# imxbbmmc.net
KiCad netlist of a schematic drawn in Altium Designer
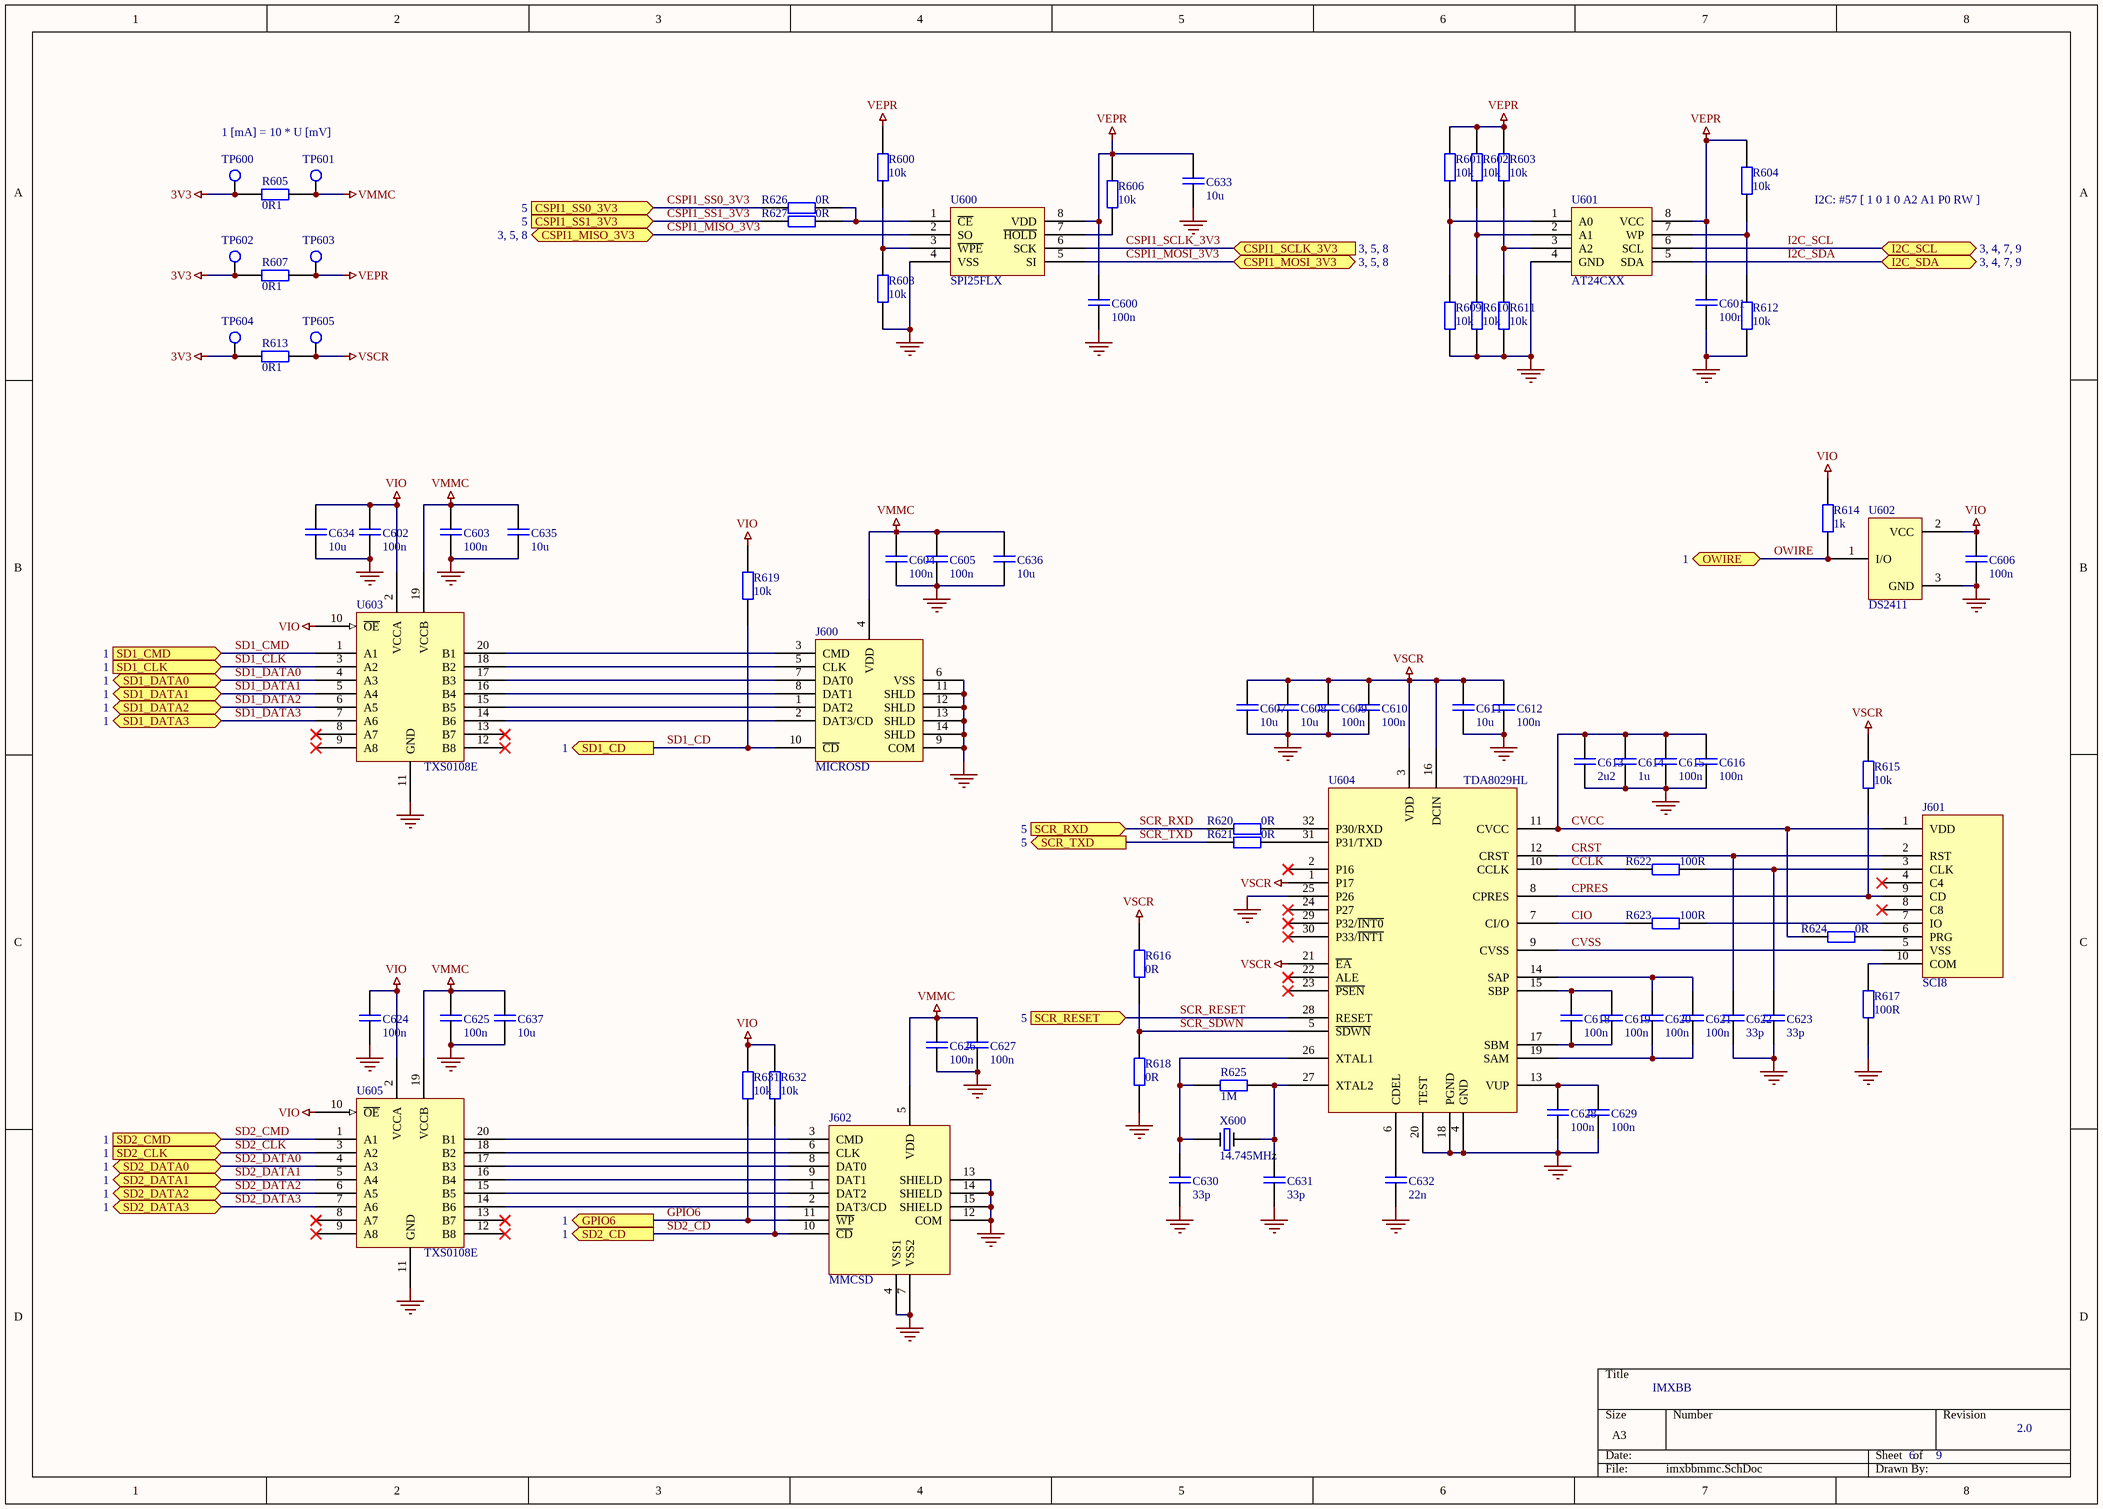
[diagram p0: imxbbmmc.SchDoc]

(export (version "E")
  (design (tool "Eeschema 10.0.6"))
  (components
    (comp (ref "C600") (value "100n") (footprint "0603") (libsource (lib "imxbb") (part "C")))
    (comp (ref "C601") (value "100n") (footprint "0603") (libsource (lib "imxbb") (part "C")))
    (comp (ref "C602") (value "100n") (footprint "0603") (libsource (lib "imxbb") (part "C")))
    (comp (ref "C603") (value "100n") (footprint "0603") (libsource (lib "imxbb") (part "C")))
    (comp (ref "C604") (value "100n") (footprint "0603") (libsource (lib "imxbb") (part "C")))
    (comp (ref "C605") (value "100n") (footprint "0603") (libsource (lib "imxbb") (part "C")))
    (comp (ref "C606") (value "100n") (footprint "0603") (libsource (lib "imxbb") (part "C")))
    (comp (ref "C607") (value "10u") (footprint "0805") (libsource (lib "imxbb") (part "C")))
    (comp (ref "C608") (value "10u") (footprint "0805") (libsource (lib "imxbb") (part "C")))
    (comp (ref "C609") (value "100n") (footprint "0603") (libsource (lib "imxbb") (part "C")))
    (comp (ref "C610") (value "100n") (footprint "0603") (libsource (lib "imxbb") (part "C")))
    (comp (ref "C611") (value "10u") (footprint "0805") (libsource (lib "imxbb") (part "C")))
    (comp (ref "C612") (value "100n") (footprint "0603") (libsource (lib "imxbb") (part "C")))
    (comp (ref "C613") (value "2u2") (footprint "0603") (libsource (lib "imxbb") (part "C")))
    (comp (ref "C614") (value "1u") (footprint "0603") (libsource (lib "imxbb") (part "C")))
    (comp (ref "C615") (value "100n") (footprint "0603") (libsource (lib "imxbb") (part "C")))
    (comp (ref "C616") (value "100n") (footprint "0603") (libsource (lib "imxbb") (part "C")))
    (comp (ref "C618") (value "100n") (footprint "0603") (libsource (lib "imxbb") (part "C")))
    (comp (ref "C619") (value "100n") (footprint "0603") (libsource (lib "imxbb") (part "C")))
    (comp (ref "C620") (value "100n") (footprint "0603") (libsource (lib "imxbb") (part "C")))
    (comp (ref "C621") (value "100n") (footprint "0603") (libsource (lib "imxbb") (part "C")))
    (comp (ref "C622") (value "33p") (footprint "0603") (libsource (lib "imxbb") (part "C")))
    (comp (ref "C623") (value "33p") (footprint "0603") (libsource (lib "imxbb") (part "C")))
    (comp (ref "C624") (value "100n") (footprint "0603") (libsource (lib "imxbb") (part "C")))
    (comp (ref "C625") (value "100n") (footprint "0603") (libsource (lib "imxbb") (part "C")))
    (comp (ref "C626") (value "100n") (footprint "0603") (libsource (lib "imxbb") (part "C")))
    (comp (ref "C627") (value "100n") (footprint "0603") (libsource (lib "imxbb") (part "C")))
    (comp (ref "C628") (value "100n") (footprint "0603") (libsource (lib "imxbb") (part "C")))
    (comp (ref "C629") (value "100n") (footprint "0603") (libsource (lib "imxbb") (part "C")))
    (comp (ref "C630") (value "33p") (footprint "0603") (libsource (lib "imxbb") (part "C")))
    (comp (ref "C631") (value "33p") (footprint "0603") (libsource (lib "imxbb") (part "C")))
    (comp (ref "C632") (value "22n") (footprint "0603") (libsource (lib "imxbb") (part "C")))
    (comp (ref "C633") (value "10u") (footprint "0805") (libsource (lib "imxbb") (part "C")))
    (comp (ref "C634") (value "10u") (footprint "0805") (libsource (lib "imxbb") (part "C")))
    (comp (ref "C635") (value "10u") (footprint "0805") (libsource (lib "imxbb") (part "C")))
    (comp (ref "C636") (value "10u") (footprint "0805") (libsource (lib "imxbb") (part "C")))
    (comp (ref "C637") (value "10u") (footprint "0805") (libsource (lib "imxbb") (part "C")))
    (comp (ref "J600") (value "MICROSD") (footprint "uSD10") (libsource (lib "imxbb") (part "MICROSD")))
    (comp (ref "J601") (value "SCI8") (footprint "SCI8F") (libsource (lib "imxbb") (part "SCI8")))
    (comp (ref "J602") (value "MMCSD") (footprint "SDCMF-109") (libsource (lib "imxbb") (part "MMCSD")))
    (comp (ref "R600") (value "10k") (footprint "0603") (libsource (lib "") (part "R_3")))
    (comp (ref "R601") (value "10k") (footprint "0603") (libsource (lib "") (part "R_3")))
    (comp (ref "R602") (value "10k") (footprint "0603") (libsource (lib "") (part "R_3")))
    (comp (ref "R603") (value "10k") (footprint "0603") (libsource (lib "") (part "R_3")))
    (comp (ref "R604") (value "10k") (footprint "0603") (libsource (lib "") (part "R_3")))
    (comp (ref "R605") (value "0R1") (footprint "0603") (libsource (lib "imxbb") (part "R")))
    (comp (ref "R606") (value "10k") (footprint "0603") (libsource (lib "") (part "R_3")))
    (comp (ref "R607") (value "0R1") (footprint "0603") (libsource (lib "imxbb") (part "R")))
    (comp (ref "R608") (value "10k") (footprint "0603") (libsource (lib "") (part "R_3")))
    (comp (ref "R609") (value "10k") (footprint "0603") (libsource (lib "") (part "R_3")))
    (comp (ref "R610") (value "10k") (footprint "0603") (libsource (lib "") (part "R_3")))
    (comp (ref "R611") (value "10k") (footprint "0603") (libsource (lib "") (part "R_3")))
    (comp (ref "R612") (value "10k") (footprint "0603") (libsource (lib "") (part "R_3")))
    (comp (ref "R613") (value "0R1") (footprint "0603") (libsource (lib "imxbb") (part "R")))
    (comp (ref "R614") (value "1k") (footprint "0603") (libsource (lib "") (part "R_3")))
    (comp (ref "R615") (value "10k") (footprint "0603") (libsource (lib "") (part "R_4")))
    (comp (ref "R616") (value "0R") (footprint "0603") (libsource (lib "") (part "R_4")))
    (comp (ref "R617") (value "100R") (footprint "0603") (libsource (lib "") (part "R_4")))
    (comp (ref "R618") (value "0R") (footprint "0603") (libsource (lib "") (part "R_4")))
    (comp (ref "R619") (value "10k") (footprint "0603") (libsource (lib "") (part "R_3")))
    (comp (ref "R620") (value "0R") (footprint "0603") (libsource (lib "") (part "R_1")))
    (comp (ref "R621") (value "0R") (footprint "0603") (libsource (lib "") (part "R_1")))
    (comp (ref "R622") (value "100R") (footprint "0603") (libsource (lib "") (part "R_1")))
    (comp (ref "R623") (value "100R") (footprint "0603") (libsource (lib "") (part "R_1")))
    (comp (ref "R624") (value "0R") (footprint "0603") (libsource (lib "") (part "R_1")))
    (comp (ref "R625") (value "1M") (footprint "0603") (libsource (lib "") (part "R_2")))
    (comp (ref "R626") (value "0R") (footprint "0603") (libsource (lib "") (part "R_1")))
    (comp (ref "R627") (value "0R") (footprint "0603") (libsource (lib "") (part "R_1")))
    (comp (ref "R631") (value "10k") (footprint "0603") (libsource (lib "") (part "R_3")))
    (comp (ref "R632") (value "10k") (footprint "0603") (libsource (lib "") (part "R_3")))
    (comp (ref "TP600")
      (value "TESTPOINT")
      (footprint "TESTPOINT_2mm")
      (description "Testpoint pad")
      (libsource (lib "imxbb") (part "TESTPOINT"))
    )
    (comp (ref "TP601")
      (value "TESTPOINT")
      (footprint "TESTPOINT_2mm")
      (description "Testpoint pad")
      (libsource (lib "imxbb") (part "TESTPOINT"))
    )
    (comp (ref "TP602")
      (value "TESTPOINT")
      (footprint "TESTPOINT_2mm")
      (description "Testpoint pad")
      (libsource (lib "imxbb") (part "TESTPOINT"))
    )
    (comp (ref "TP603")
      (value "TESTPOINT")
      (footprint "TESTPOINT_2mm")
      (description "Testpoint pad")
      (libsource (lib "imxbb") (part "TESTPOINT"))
    )
    (comp (ref "TP604")
      (value "TESTPOINT")
      (footprint "TESTPOINT_2mm")
      (description "Testpoint pad")
      (libsource (lib "imxbb") (part "TESTPOINT"))
    )
    (comp (ref "TP605")
      (value "TESTPOINT")
      (footprint "TESTPOINT_2mm")
      (description "Testpoint pad")
      (libsource (lib "imxbb") (part "TESTPOINT"))
    )
    (comp (ref "U600") (value "SPI25FLX") (footprint "SOIC8") (libsource (lib "imxbb") (part "SPI25FLX")))
    (comp (ref "U601") (value "AT24CXX") (footprint "SOIC8") (libsource (lib "imxbb") (part "AT24CXX")))
    (comp (ref "U602") (value "DS2411") (footprint "SOT23") (libsource (lib "imxbb") (part "DS2411")))
    (comp (ref "U603") (value "TXS0108E") (footprint "TSSOP20") (libsource (lib "imxbb") (part "TXS0108E")))
    (comp (ref "U604") (value "TDA8029HL") (footprint "LQFP32") (libsource (lib "imxbb") (part "TDA8029HL")))
    (comp (ref "U605") (value "TXS0108E") (footprint "TSSOP20") (libsource (lib "imxbb") (part "TXS0108E")))
    (comp (ref "X600") (value "14.745MHz") (footprint "HC494H") (libsource (lib "imxbb") (part "XTAL")))
  )
  (nets
    (net (code "1") (name "/CCLK") (class "Default")
      (node (ref "R622") (pin "1") (pinfunction "1_1") (pintype "passive"))
      (node (ref "U604") (pin "10") (pinfunction "CCLK_10") (pintype "passive"))
    )
    (net (code "2") (name "/CIO") (class "Default")
      (node (ref "R623") (pin "1") (pinfunction "1_1") (pintype "passive"))
      (node (ref "U604") (pin "7") (pinfunction "CI/O_7") (pintype "passive"))
    )
    (net (code "3") (name "/CPRES") (class "Default")
      (node (ref "J601") (pin "9") (pinfunction "CD_9") (pintype "passive"))
      (node (ref "R615") (pin "1") (pinfunction "1_1") (pintype "passive"))
      (node (ref "U604") (pin "8") (pinfunction "CPRES_8") (pintype "passive"))
    )
    (net (code "4") (name "/CRST") (class "Default")
      (node (ref "C622") (pin "2") (pinfunction "2_2") (pintype "passive"))
      (node (ref "J601") (pin "2") (pinfunction "RST_2") (pintype "passive"))
      (node (ref "U604") (pin "12") (pinfunction "CRST_12") (pintype "passive"))
    )
    (net (code "5") (name "/CSPI1_MISO_3V3") (class "Default")
      (node (ref "U600") (pin "2") (pinfunction "SO_2") (pintype "passive"))
    )
    (net (code "6") (name "/CSPI1_MOSI_3V3") (class "Default")
      (node (ref "U600") (pin "5") (pinfunction "SI_5") (pintype "passive"))
    )
    (net (code "7") (name "/CSPI1_SCLK_3V3") (class "Default")
      (node (ref "U600") (pin "6") (pinfunction "SCK_6") (pintype "passive"))
    )
    (net (code "8") (name "/CSPI1_SS0_3V3") (class "Default")
      (node (ref "R626") (pin "1") (pinfunction "1_1") (pintype "passive"))
    )
    (net (code "9") (name "/CSPI1_SS1_3V3") (class "Default")
      (node (ref "R627") (pin "1") (pinfunction "1_1") (pintype "passive"))
    )
    (net (code "10") (name "/CVCC") (class "Default")
      (node (ref "C613") (pin "2") (pinfunction "2_2") (pintype "passive"))
      (node (ref "C614") (pin "2") (pinfunction "2_2") (pintype "passive"))
      (node (ref "C615") (pin "2") (pinfunction "2_2") (pintype "passive"))
      (node (ref "C616") (pin "2") (pinfunction "2_2") (pintype "passive"))
      (node (ref "J601") (pin "1") (pinfunction "VDD_1") (pintype "passive"))
      (node (ref "R624") (pin "1") (pinfunction "1_1") (pintype "passive"))
      (node (ref "U604") (pin "11") (pinfunction "CVCC_11") (pintype "passive"))
    )
    (net (code "11") (name "/CVSS") (class "Default")
      (node (ref "J601") (pin "5") (pinfunction "VSS_5") (pintype "passive"))
      (node (ref "U604") (pin "9") (pinfunction "CVSS_9") (pintype "passive"))
    )
    (net (code "12") (name "/GPIO6") (class "Default")
      (node (ref "J602") (pin "11") (pinfunction "~{WP}_11") (pintype "passive"))
      (node (ref "R631") (pin "2") (pinfunction "2_2") (pintype "passive"))
    )
    (net (code "13") (name "/I2C_SCL") (class "Default")
      (node (ref "U601") (pin "6") (pinfunction "SCL_6") (pintype "passive"))
    )
    (net (code "14") (name "/I2C_SDA") (class "Default")
      (node (ref "U601") (pin "5") (pinfunction "SDA_5") (pintype "passive"))
    )
    (net (code "15") (name "/OWIRE") (class "Default")
      (node (ref "R614") (pin "2") (pinfunction "2_2") (pintype "passive"))
      (node (ref "U602") (pin "1") (pinfunction "I/O_1") (pintype "passive"))
    )
    (net (code "16") (name "/SCR_RESET") (class "Default")
      (node (ref "U604") (pin "28") (pinfunction "RESET_28") (pintype "passive"))
    )
    (net (code "17") (name "/SCR_RXD") (class "Default")
      (node (ref "R620") (pin "1") (pinfunction "1_1") (pintype "passive"))
    )
    (net (code "18") (name "/SCR_SDWN") (class "Default")
      (node (ref "R616") (pin "1") (pinfunction "1_1") (pintype "passive"))
      (node (ref "R618") (pin "2") (pinfunction "2_2") (pintype "passive"))
      (node (ref "U604") (pin "5") (pinfunction "~{SDWN}_5") (pintype "passive"))
    )
    (net (code "19") (name "/SCR_TXD") (class "Default")
      (node (ref "R621") (pin "1") (pinfunction "1_1") (pintype "passive"))
    )
    (net (code "20") (name "/SD1_CD") (class "Default")
      (node (ref "J600") (pin "10") (pinfunction "~{CD}_10") (pintype "passive"))
      (node (ref "R619") (pin "2") (pinfunction "2_2") (pintype "passive"))
    )
    (net (code "21") (name "/SD1_CLK") (class "Default")
      (node (ref "U603") (pin "3") (pinfunction "A2_3") (pintype "passive"))
    )
    (net (code "22") (name "/SD1_CMD") (class "Default")
      (node (ref "U603") (pin "1") (pinfunction "A1_1") (pintype "passive"))
    )
    (net (code "23") (name "/SD1_DATA0") (class "Default")
      (node (ref "U603") (pin "4") (pinfunction "A3_4") (pintype "passive"))
    )
    (net (code "24") (name "/SD1_DATA1") (class "Default")
      (node (ref "U603") (pin "5") (pinfunction "A4_5") (pintype "passive"))
    )
    (net (code "25") (name "/SD1_DATA2") (class "Default")
      (node (ref "U603") (pin "6") (pinfunction "A5_6") (pintype "passive"))
    )
    (net (code "26") (name "/SD1_DATA3") (class "Default")
      (node (ref "U603") (pin "7") (pinfunction "A6_7") (pintype "passive"))
    )
    (net (code "27") (name "/SD2_CD") (class "Default")
      (node (ref "J602") (pin "10") (pinfunction "~{CD}_10") (pintype "passive"))
      (node (ref "R632") (pin "2") (pinfunction "2_2") (pintype "passive"))
    )
    (net (code "28") (name "/SD2_CLK") (class "Default")
      (node (ref "U605") (pin "3") (pinfunction "A2_3") (pintype "passive"))
    )
    (net (code "29") (name "/SD2_CMD") (class "Default")
      (node (ref "U605") (pin "1") (pinfunction "A1_1") (pintype "passive"))
    )
    (net (code "30") (name "/SD2_DATA0") (class "Default")
      (node (ref "U605") (pin "4") (pinfunction "A3_4") (pintype "passive"))
    )
    (net (code "31") (name "/SD2_DATA1") (class "Default")
      (node (ref "U605") (pin "5") (pinfunction "A4_5") (pintype "passive"))
    )
    (net (code "32") (name "/SD2_DATA2") (class "Default")
      (node (ref "U605") (pin "6") (pinfunction "A5_6") (pintype "passive"))
    )
    (net (code "33") (name "/SD2_DATA3") (class "Default")
      (node (ref "U605") (pin "7") (pinfunction "A6_7") (pintype "passive"))
    )
    (net (code "34") (name "3V3") (class "Default")
      (node (ref "R605") (pin "1") (pinfunction "1_1") (pintype "passive"))
      (node (ref "R607") (pin "1") (pinfunction "1_1") (pintype "passive"))
      (node (ref "R613") (pin "1") (pinfunction "1_1") (pintype "passive"))
      (node (ref "TP600") (pin "1") (pinfunction "1_1") (pintype "passive"))
      (node (ref "TP602") (pin "1") (pinfunction "1_1") (pintype "passive"))
      (node (ref "TP604") (pin "1") (pinfunction "1_1") (pintype "passive"))
    )
    (net (code "35") (name "GND") (class "Default")
      (node (ref "C600") (pin "1") (pinfunction "1_1") (pintype "passive"))
      (node (ref "C601") (pin "1") (pinfunction "1_1") (pintype "passive"))
      (node (ref "C602") (pin "1") (pinfunction "1_1") (pintype "passive"))
      (node (ref "C603") (pin "1") (pinfunction "1_1") (pintype "passive"))
      (node (ref "C604") (pin "1") (pinfunction "1_1") (pintype "passive"))
      (node (ref "C605") (pin "1") (pinfunction "1_1") (pintype "passive"))
      (node (ref "C606") (pin "1") (pinfunction "1_1") (pintype "passive"))
      (node (ref "C607") (pin "1") (pinfunction "1_1") (pintype "passive"))
      (node (ref "C608") (pin "1") (pinfunction "1_1") (pintype "passive"))
      (node (ref "C609") (pin "1") (pinfunction "1_1") (pintype "passive"))
      (node (ref "C610") (pin "1") (pinfunction "1_1") (pintype "passive"))
      (node (ref "C611") (pin "1") (pinfunction "1_1") (pintype "passive"))
      (node (ref "C612") (pin "1") (pinfunction "1_1") (pintype "passive"))
      (node (ref "C613") (pin "1") (pinfunction "1_1") (pintype "passive"))
      (node (ref "C614") (pin "1") (pinfunction "1_1") (pintype "passive"))
      (node (ref "C615") (pin "1") (pinfunction "1_1") (pintype "passive"))
      (node (ref "C616") (pin "1") (pinfunction "1_1") (pintype "passive"))
      (node (ref "C622") (pin "1") (pinfunction "1_1") (pintype "passive"))
      (node (ref "C623") (pin "1") (pinfunction "1_1") (pintype "passive"))
      (node (ref "C624") (pin "1") (pinfunction "1_1") (pintype "passive"))
      (node (ref "C625") (pin "1") (pinfunction "1_1") (pintype "passive"))
      (node (ref "C626") (pin "1") (pinfunction "1_1") (pintype "passive"))
      (node (ref "C627") (pin "1") (pinfunction "1_1") (pintype "passive"))
      (node (ref "C628") (pin "1") (pinfunction "1_1") (pintype "passive"))
      (node (ref "C629") (pin "1") (pinfunction "1_1") (pintype "passive"))
      (node (ref "C630") (pin "1") (pinfunction "1_1") (pintype "passive"))
      (node (ref "C631") (pin "1") (pinfunction "1_1") (pintype "passive"))
      (node (ref "C632") (pin "1") (pinfunction "1_1") (pintype "passive"))
      (node (ref "C633") (pin "1") (pinfunction "1_1") (pintype "passive"))
      (node (ref "C634") (pin "1") (pinfunction "1_1") (pintype "passive"))
      (node (ref "C635") (pin "1") (pinfunction "1_1") (pintype "passive"))
      (node (ref "C636") (pin "1") (pinfunction "1_1") (pintype "passive"))
      (node (ref "C637") (pin "1") (pinfunction "1_1") (pintype "passive"))
      (node (ref "J600") (pin "11") (pinfunction "SHLD_11") (pintype "passive"))
      (node (ref "J600") (pin "12") (pinfunction "SHLD_12") (pintype "passive"))
      (node (ref "J600") (pin "13") (pinfunction "SHLD_13") (pintype "passive"))
      (node (ref "J600") (pin "14") (pinfunction "SHLD_14") (pintype "passive"))
      (node (ref "J600") (pin "6") (pinfunction "VSS_6") (pintype "passive"))
      (node (ref "J600") (pin "9") (pinfunction "COM_9") (pintype "passive"))
      (node (ref "J602") (pin "12") (pinfunction "COM_12") (pintype "passive"))
      (node (ref "J602") (pin "13") (pinfunction "SHIELD_13") (pintype "passive"))
      (node (ref "J602") (pin "14") (pinfunction "SHIELD_14") (pintype "passive"))
      (node (ref "J602") (pin "15") (pinfunction "SHIELD_15") (pintype "passive"))
      (node (ref "J602") (pin "4") (pinfunction "VSS1_4") (pintype "passive"))
      (node (ref "J602") (pin "7") (pinfunction "VSS2_7") (pintype "passive"))
      (node (ref "R608") (pin "2") (pinfunction "2_2") (pintype "passive"))
      (node (ref "R609") (pin "2") (pinfunction "2_2") (pintype "passive"))
      (node (ref "R610") (pin "2") (pinfunction "2_2") (pintype "passive"))
      (node (ref "R611") (pin "2") (pinfunction "2_2") (pintype "passive"))
      (node (ref "R612") (pin "2") (pinfunction "2_2") (pintype "passive"))
      (node (ref "R617") (pin "1") (pinfunction "1_1") (pintype "passive"))
      (node (ref "R618") (pin "1") (pinfunction "1_1") (pintype "passive"))
      (node (ref "U600") (pin "4") (pinfunction "VSS_4") (pintype "passive"))
      (node (ref "U601") (pin "4") (pinfunction "GND_4") (pintype "passive"))
      (node (ref "U602") (pin "3") (pinfunction "GND_3") (pintype "passive"))
      (node (ref "U603") (pin "11") (pinfunction "GND_11") (pintype "power_in"))
      (node (ref "U604") (pin "18") (pinfunction "PGND_18") (pintype "passive"))
      (node (ref "U604") (pin "20") (pinfunction "TEST_20") (pintype "passive"))
      (node (ref "U604") (pin "25") (pinfunction "P26_25") (pintype "passive"))
      (node (ref "U604") (pin "4") (pinfunction "GND_4") (pintype "passive"))
      (node (ref "U605") (pin "11") (pinfunction "GND_11") (pintype "power_in"))
    )
    (net (code "36") (name "Net-(J600-CLK)") (class "Default")
      (node (ref "J600") (pin "5") (pinfunction "CLK_5") (pintype "passive"))
      (node (ref "U603") (pin "18") (pinfunction "B2_18") (pintype "passive"))
    )
    (net (code "37") (name "Net-(J600-CMD)") (class "Default")
      (node (ref "J600") (pin "3") (pinfunction "CMD_3") (pintype "passive"))
      (node (ref "U603") (pin "20") (pinfunction "B1_20") (pintype "passive"))
    )
    (net (code "38") (name "Net-(J600-DAT0)") (class "Default")
      (node (ref "J600") (pin "7") (pinfunction "DAT0_7") (pintype "passive"))
      (node (ref "U603") (pin "17") (pinfunction "B3_17") (pintype "passive"))
    )
    (net (code "39") (name "Net-(J600-DAT1)") (class "Default")
      (node (ref "J600") (pin "8") (pinfunction "DAT1_8") (pintype "passive"))
      (node (ref "U603") (pin "16") (pinfunction "B4_16") (pintype "passive"))
    )
    (net (code "40") (name "Net-(J600-DAT2)") (class "Default")
      (node (ref "J600") (pin "1") (pinfunction "DAT2_1") (pintype "passive"))
      (node (ref "U603") (pin "15") (pinfunction "B5_15") (pintype "passive"))
    )
    (net (code "41") (name "Net-(J600-DAT3{slash}CD)") (class "Default")
      (node (ref "J600") (pin "2") (pinfunction "DAT3/CD_2") (pintype "passive"))
      (node (ref "U603") (pin "14") (pinfunction "B6_14") (pintype "passive"))
    )
    (net (code "42") (name "Net-(J601-CLK)") (class "Default")
      (node (ref "C623") (pin "2") (pinfunction "2_2") (pintype "passive"))
      (node (ref "J601") (pin "3") (pinfunction "CLK_3") (pintype "passive"))
      (node (ref "R622") (pin "2") (pinfunction "2_2") (pintype "passive"))
    )
    (net (code "43") (name "Net-(J601-COM)") (class "Default")
      (node (ref "J601") (pin "10") (pinfunction "COM_10") (pintype "passive"))
      (node (ref "R617") (pin "2") (pinfunction "2_2") (pintype "passive"))
    )
    (net (code "44") (name "Net-(J601-IO)") (class "Default")
      (node (ref "J601") (pin "7") (pinfunction "IO_7") (pintype "passive"))
      (node (ref "R623") (pin "2") (pinfunction "2_2") (pintype "passive"))
    )
    (net (code "45") (name "Net-(J601-PRG)") (class "Default")
      (node (ref "J601") (pin "6") (pinfunction "PRG_6") (pintype "passive"))
      (node (ref "R624") (pin "2") (pinfunction "2_2") (pintype "passive"))
    )
    (net (code "46") (name "Net-(J602-CLK)") (class "Default")
      (node (ref "J602") (pin "6") (pinfunction "CLK_6") (pintype "passive"))
      (node (ref "U605") (pin "18") (pinfunction "B2_18") (pintype "passive"))
    )
    (net (code "47") (name "Net-(J602-CMD)") (class "Default")
      (node (ref "J602") (pin "3") (pinfunction "CMD_3") (pintype "passive"))
      (node (ref "U605") (pin "20") (pinfunction "B1_20") (pintype "passive"))
    )
    (net (code "48") (name "Net-(J602-DAT0)") (class "Default")
      (node (ref "J602") (pin "8") (pinfunction "DAT0_8") (pintype "passive"))
      (node (ref "U605") (pin "17") (pinfunction "B3_17") (pintype "passive"))
    )
    (net (code "49") (name "Net-(J602-DAT1)") (class "Default")
      (node (ref "J602") (pin "9") (pinfunction "DAT1_9") (pintype "passive"))
      (node (ref "U605") (pin "16") (pinfunction "B4_16") (pintype "passive"))
    )
    (net (code "50") (name "Net-(J602-DAT2)") (class "Default")
      (node (ref "J602") (pin "1") (pinfunction "DAT2_1") (pintype "passive"))
      (node (ref "U605") (pin "15") (pinfunction "B5_15") (pintype "passive"))
    )
    (net (code "51") (name "Net-(J602-DAT3{slash}CD)") (class "Default")
      (node (ref "J602") (pin "2") (pinfunction "DAT3/CD_2") (pintype "passive"))
      (node (ref "U605") (pin "14") (pinfunction "B6_14") (pintype "passive"))
    )
    (net (code "52") (name "Net-(U600-~{CE})") (class "Default")
      (node (ref "R626") (pin "2") (pinfunction "2_2") (pintype "passive"))
      (node (ref "R627") (pin "2") (pinfunction "2_2") (pintype "passive"))
      (node (ref "U600") (pin "1") (pinfunction "~{CE}_1") (pintype "passive"))
    )
    (net (code "53") (name "Net-(U600-~{HOLD})") (class "Default")
      (node (ref "R606") (pin "2") (pinfunction "2_2") (pintype "passive"))
      (node (ref "U600") (pin "7") (pinfunction "~{HOLD}_7") (pintype "passive"))
    )
    (net (code "54") (name "Net-(U600-~{WPE})") (class "Default")
      (node (ref "R600") (pin "2") (pinfunction "2_2") (pintype "passive"))
      (node (ref "R608") (pin "1") (pinfunction "1_1") (pintype "passive"))
      (node (ref "U600") (pin "3") (pinfunction "~{WPE}_3") (pintype "passive"))
    )
    (net (code "55") (name "Net-(U601-A0)") (class "Default")
      (node (ref "R601") (pin "2") (pinfunction "2_2") (pintype "passive"))
      (node (ref "R609") (pin "1") (pinfunction "1_1") (pintype "passive"))
      (node (ref "U601") (pin "1") (pinfunction "A0_1") (pintype "passive"))
    )
    (net (code "56") (name "Net-(U601-A1)") (class "Default")
      (node (ref "R602") (pin "2") (pinfunction "2_2") (pintype "passive"))
      (node (ref "R610") (pin "1") (pinfunction "1_1") (pintype "passive"))
      (node (ref "U601") (pin "2") (pinfunction "A1_2") (pintype "passive"))
    )
    (net (code "57") (name "Net-(U601-A2)") (class "Default")
      (node (ref "R603") (pin "2") (pinfunction "2_2") (pintype "passive"))
      (node (ref "R611") (pin "1") (pinfunction "1_1") (pintype "passive"))
      (node (ref "U601") (pin "3") (pinfunction "A2_3") (pintype "passive"))
    )
    (net (code "58") (name "Net-(U601-WP)") (class "Default")
      (node (ref "R604") (pin "2") (pinfunction "2_2") (pintype "passive"))
      (node (ref "R612") (pin "1") (pinfunction "1_1") (pintype "passive"))
      (node (ref "U601") (pin "7") (pinfunction "WP_7") (pintype "passive"))
    )
    (net (code "59") (name "Net-(U604-CDEL)") (class "Default")
      (node (ref "C632") (pin "2") (pinfunction "2_2") (pintype "passive"))
      (node (ref "U604") (pin "6") (pinfunction "CDEL_6") (pintype "passive"))
    )
    (net (code "60") (name "Net-(U604-P30{slash}RXD)") (class "Default")
      (node (ref "R620") (pin "2") (pinfunction "2_2") (pintype "passive"))
      (node (ref "U604") (pin "32") (pinfunction "P30/RXD_32") (pintype "passive"))
    )
    (net (code "61") (name "Net-(U604-P31{slash}TXD)") (class "Default")
      (node (ref "R621") (pin "2") (pinfunction "2_2") (pintype "passive"))
      (node (ref "U604") (pin "31") (pinfunction "P31/TXD_31") (pintype "passive"))
    )
    (net (code "62") (name "Net-(U604-SAM)") (class "Default")
      (node (ref "C620") (pin "1") (pinfunction "1_1") (pintype "passive"))
      (node (ref "C621") (pin "1") (pinfunction "1_1") (pintype "passive"))
      (node (ref "U604") (pin "19") (pinfunction "SAM_19") (pintype "passive"))
    )
    (net (code "63") (name "Net-(U604-SAP)") (class "Default")
      (node (ref "C620") (pin "2") (pinfunction "2_2") (pintype "passive"))
      (node (ref "C621") (pin "2") (pinfunction "2_2") (pintype "passive"))
      (node (ref "U604") (pin "14") (pinfunction "SAP_14") (pintype "passive"))
    )
    (net (code "64") (name "Net-(U604-SBM)") (class "Default")
      (node (ref "C618") (pin "1") (pinfunction "1_1") (pintype "passive"))
      (node (ref "C619") (pin "1") (pinfunction "1_1") (pintype "passive"))
      (node (ref "U604") (pin "17") (pinfunction "SBM_17") (pintype "passive"))
    )
    (net (code "65") (name "Net-(U604-SBP)") (class "Default")
      (node (ref "C618") (pin "2") (pinfunction "2_2") (pintype "passive"))
      (node (ref "C619") (pin "2") (pinfunction "2_2") (pintype "passive"))
      (node (ref "U604") (pin "15") (pinfunction "SBP_15") (pintype "passive"))
    )
    (net (code "66") (name "Net-(U604-VUP)") (class "Default")
      (node (ref "C628") (pin "2") (pinfunction "2_2") (pintype "passive"))
      (node (ref "C629") (pin "2") (pinfunction "2_2") (pintype "passive"))
      (node (ref "U604") (pin "13") (pinfunction "VUP_13") (pintype "passive"))
    )
    (net (code "67") (name "Net-(U604-XTAL1)") (class "Default")
      (node (ref "C630") (pin "2") (pinfunction "2_2") (pintype "passive"))
      (node (ref "R625") (pin "2") (pinfunction "2_2") (pintype "passive"))
      (node (ref "U604") (pin "26") (pinfunction "XTAL1_26") (pintype "passive"))
      (node (ref "X600") (pin "1") (pinfunction "1_1") (pintype "passive"))
    )
    (net (code "68") (name "Net-(U604-XTAL2)") (class "Default")
      (node (ref "C631") (pin "2") (pinfunction "2_2") (pintype "passive"))
      (node (ref "R625") (pin "1") (pinfunction "1_1") (pintype "passive"))
      (node (ref "U604") (pin "27") (pinfunction "XTAL2_27") (pintype "passive"))
      (node (ref "X600") (pin "2") (pinfunction "2_2") (pintype "passive"))
    )
    (net (code "69") (name "VEPR") (class "Default")
      (node (ref "C600") (pin "2") (pinfunction "2_2") (pintype "passive"))
      (node (ref "C601") (pin "2") (pinfunction "2_2") (pintype "passive"))
      (node (ref "C633") (pin "2") (pinfunction "2_2") (pintype "passive"))
      (node (ref "R600") (pin "1") (pinfunction "1_1") (pintype "passive"))
      (node (ref "R601") (pin "1") (pinfunction "1_1") (pintype "passive"))
      (node (ref "R602") (pin "1") (pinfunction "1_1") (pintype "passive"))
      (node (ref "R603") (pin "1") (pinfunction "1_1") (pintype "passive"))
      (node (ref "R604") (pin "1") (pinfunction "1_1") (pintype "passive"))
      (node (ref "R606") (pin "1") (pinfunction "1_1") (pintype "passive"))
      (node (ref "R607") (pin "2") (pinfunction "2_2") (pintype "passive"))
      (node (ref "TP603") (pin "1") (pinfunction "1_1") (pintype "passive"))
      (node (ref "U600") (pin "8") (pinfunction "VDD_8") (pintype "passive"))
      (node (ref "U601") (pin "8") (pinfunction "VCC_8") (pintype "passive"))
    )
    (net (code "70") (name "VIO") (class "Default")
      (node (ref "C602") (pin "2") (pinfunction "2_2") (pintype "passive"))
      (node (ref "C606") (pin "2") (pinfunction "2_2") (pintype "passive"))
      (node (ref "C624") (pin "2") (pinfunction "2_2") (pintype "passive"))
      (node (ref "C634") (pin "2") (pinfunction "2_2") (pintype "passive"))
      (node (ref "R614") (pin "1") (pinfunction "1_1") (pintype "passive"))
      (node (ref "R619") (pin "1") (pinfunction "1_1") (pintype "passive"))
      (node (ref "R631") (pin "1") (pinfunction "1_1") (pintype "passive"))
      (node (ref "R632") (pin "1") (pinfunction "1_1") (pintype "passive"))
      (node (ref "U602") (pin "2") (pinfunction "VCC_2") (pintype "passive"))
      (node (ref "U603") (pin "10") (pinfunction "~{OE}_10") (pintype "input"))
      (node (ref "U603") (pin "2") (pinfunction "VCCA_2") (pintype "power_in"))
      (node (ref "U605") (pin "10") (pinfunction "~{OE}_10") (pintype "input"))
      (node (ref "U605") (pin "2") (pinfunction "VCCA_2") (pintype "power_in"))
    )
    (net (code "71") (name "VMMC") (class "Default")
      (node (ref "C603") (pin "2") (pinfunction "2_2") (pintype "passive"))
      (node (ref "C604") (pin "2") (pinfunction "2_2") (pintype "passive"))
      (node (ref "C605") (pin "2") (pinfunction "2_2") (pintype "passive"))
      (node (ref "C625") (pin "2") (pinfunction "2_2") (pintype "passive"))
      (node (ref "C626") (pin "2") (pinfunction "2_2") (pintype "passive"))
      (node (ref "C627") (pin "2") (pinfunction "2_2") (pintype "passive"))
      (node (ref "C635") (pin "2") (pinfunction "2_2") (pintype "passive"))
      (node (ref "C636") (pin "2") (pinfunction "2_2") (pintype "passive"))
      (node (ref "C637") (pin "2") (pinfunction "2_2") (pintype "passive"))
      (node (ref "J600") (pin "4") (pinfunction "VDD_4") (pintype "passive"))
      (node (ref "J602") (pin "5") (pinfunction "VDD_5") (pintype "passive"))
      (node (ref "R605") (pin "2") (pinfunction "2_2") (pintype "passive"))
      (node (ref "TP601") (pin "1") (pinfunction "1_1") (pintype "passive"))
      (node (ref "U603") (pin "19") (pinfunction "VCCB_19") (pintype "power_in"))
      (node (ref "U605") (pin "19") (pinfunction "VCCB_19") (pintype "power_in"))
    )
    (net (code "72") (name "VSCR") (class "Default")
      (node (ref "C607") (pin "2") (pinfunction "2_2") (pintype "passive"))
      (node (ref "C608") (pin "2") (pinfunction "2_2") (pintype "passive"))
      (node (ref "C609") (pin "2") (pinfunction "2_2") (pintype "passive"))
      (node (ref "C610") (pin "2") (pinfunction "2_2") (pintype "passive"))
      (node (ref "C611") (pin "2") (pinfunction "2_2") (pintype "passive"))
      (node (ref "C612") (pin "2") (pinfunction "2_2") (pintype "passive"))
      (node (ref "R613") (pin "2") (pinfunction "2_2") (pintype "passive"))
      (node (ref "R615") (pin "2") (pinfunction "2_2") (pintype "passive"))
      (node (ref "R616") (pin "2") (pinfunction "2_2") (pintype "passive"))
      (node (ref "TP605") (pin "1") (pinfunction "1_1") (pintype "passive"))
      (node (ref "U604") (pin "1") (pinfunction "P17_1") (pintype "passive"))
      (node (ref "U604") (pin "16") (pinfunction "DCIN_16") (pintype "passive"))
      (node (ref "U604") (pin "21") (pinfunction "~{EA}_21") (pintype "passive"))
      (node (ref "U604") (pin "3") (pinfunction "VDD_3") (pintype "passive"))
    )
    (net (code "73") (name "unconnected-(J601-C4-Pad4)") (class "Default")
      (node (ref "J601") (pin "4") (pinfunction "C4_4") (pintype "passive+no_connect"))
    )
    (net (code "74") (name "unconnected-(J601-C8-Pad8)") (class "Default")
      (node (ref "J601") (pin "8") (pinfunction "C8_8") (pintype "passive+no_connect"))
    )
    (net (code "75") (name "unconnected-(U603-A7-Pad8)") (class "Default")
      (node (ref "U603") (pin "8") (pinfunction "A7_8") (pintype "passive+no_connect"))
    )
    (net (code "76") (name "unconnected-(U603-A8-Pad9)") (class "Default")
      (node (ref "U603") (pin "9") (pinfunction "A8_9") (pintype "passive+no_connect"))
    )
    (net (code "77") (name "unconnected-(U603-B7-Pad13)") (class "Default")
      (node (ref "U603") (pin "13") (pinfunction "B7_13") (pintype "passive+no_connect"))
    )
    (net (code "78") (name "unconnected-(U603-B8-Pad12)") (class "Default")
      (node (ref "U603") (pin "12") (pinfunction "B8_12") (pintype "passive+no_connect"))
    )
    (net (code "79") (name "unconnected-(U604-ALE-Pad22)") (class "Default")
      (node (ref "U604") (pin "22") (pinfunction "ALE_22") (pintype "passive+no_connect"))
    )
    (net (code "80") (name "unconnected-(U604-P16-Pad2)") (class "Default")
      (node (ref "U604") (pin "2") (pinfunction "P16_2") (pintype "passive+no_connect"))
    )
    (net (code "81") (name "unconnected-(U604-P27-Pad24)") (class "Default")
      (node (ref "U604") (pin "24") (pinfunction "P27_24") (pintype "passive+no_connect"))
    )
    (net (code "82") (name "unconnected-(U604-P32{slash}~{INT0}-Pad29)") (class "Default")
      (node (ref "U604") (pin "29") (pinfunction "P32/~{INT0}_29") (pintype "passive+no_connect"))
    )
    (net (code "83") (name "unconnected-(U604-P33{slash}~{INT1}-Pad30)") (class "Default")
      (node (ref "U604") (pin "30") (pinfunction "P33/~{INT1}_30") (pintype "passive+no_connect"))
    )
    (net (code "84") (name "unconnected-(U604-~{PSEN}-Pad23)") (class "Default")
      (node (ref "U604") (pin "23") (pinfunction "~{PSEN}_23") (pintype "passive+no_connect"))
    )
    (net (code "85") (name "unconnected-(U605-A7-Pad8)") (class "Default")
      (node (ref "U605") (pin "8") (pinfunction "A7_8") (pintype "passive+no_connect"))
    )
    (net (code "86") (name "unconnected-(U605-A8-Pad9)") (class "Default")
      (node (ref "U605") (pin "9") (pinfunction "A8_9") (pintype "passive+no_connect"))
    )
    (net (code "87") (name "unconnected-(U605-B7-Pad13)") (class "Default")
      (node (ref "U605") (pin "13") (pinfunction "B7_13") (pintype "passive+no_connect"))
    )
    (net (code "88") (name "unconnected-(U605-B8-Pad12)") (class "Default")
      (node (ref "U605") (pin "12") (pinfunction "B8_12") (pintype "passive+no_connect"))
    )
  )
)
